# Sheet2.net
KiCad netlist of a schematic drawn in Altium Designer
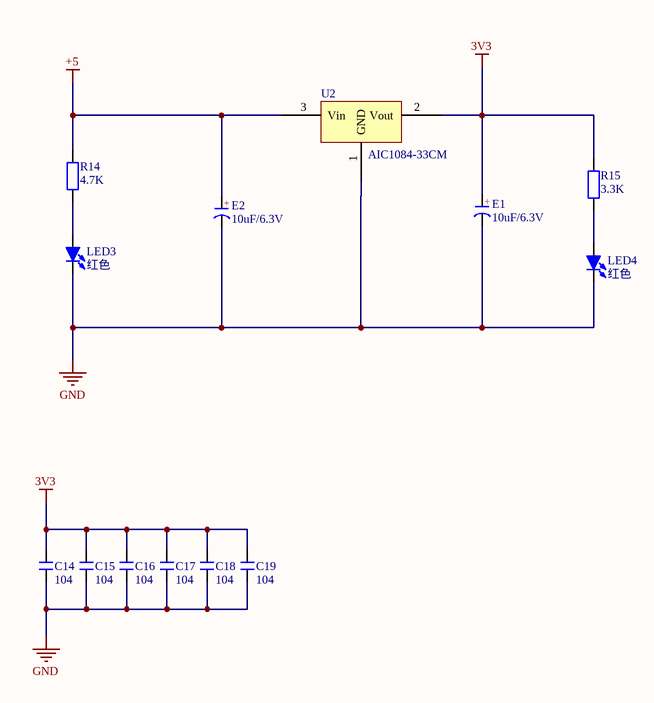
[diagram p0: Sheet2.SchDoc]

(export (version "E")
  (design (tool "Eeschema 10.0.6"))
  (components
    (comp (ref "C14")
      (value "104")
      (footprint "C 0603_L")
      (description "无极性贴片电容")
      (fields (field (name "版权归属") "源创客"))
      (libsource (lib "3.1   - 电阻-电容-电感") (part "C"))
    )
    (comp (ref "C15")
      (value "104")
      (footprint "C 0603_L")
      (description "无极性贴片电容")
      (fields (field (name "版权归属") "源创客"))
      (libsource (lib "3.1   - 电阻-电容-电感") (part "C"))
    )
    (comp (ref "C16")
      (value "104")
      (footprint "C 0603_L")
      (description "无极性贴片电容")
      (fields (field (name "版权归属") "源创客"))
      (libsource (lib "3.1   - 电阻-电容-电感") (part "C"))
    )
    (comp (ref "C17")
      (value "104")
      (footprint "C 0603_L")
      (description "无极性贴片电容")
      (fields (field (name "版权归属") "源创客"))
      (libsource (lib "3.1   - 电阻-电容-电感") (part "C"))
    )
    (comp (ref "C18")
      (value "104")
      (footprint "C 0603_L")
      (description "无极性贴片电容")
      (fields (field (name "版权归属") "源创客"))
      (libsource (lib "3.1   - 电阻-电容-电感") (part "C"))
    )
    (comp (ref "C19")
      (value "104")
      (footprint "C 0603_L")
      (description "无极性贴片电容")
      (fields (field (name "版权归属") "源创客"))
      (libsource (lib "3.1   - 电阻-电容-电感") (part "C"))
    )
    (comp (ref "E1")
      (value "10uF/6.3V")
      (footprint "CD A(3216)")
      (description "贴片钽电容")
      (fields (field (name "版权归属") "源创客"))
      (libsource (lib "3.1   - 电阻-电容-电感") (part "C-CD"))
    )
    (comp (ref "E2")
      (value "10uF/6.3V")
      (footprint "CD A(3216)")
      (description "贴片钽电容")
      (fields (field (name "版权归属") "源创客"))
      (libsource (lib "3.1   - 电阻-电容-电感") (part "C-CD"))
    )
    (comp (ref "LED3")
      (value "红色")
      (footprint "LED 0603R")
      (description "贴片LED")
      (fields (field (name "版权归属") "源创客"))
      (libsource (lib "9.1   - LED") (part "LED-SMD"))
    )
    (comp (ref "LED4")
      (value "红色")
      (footprint "LED 0603B")
      (description "贴片LED")
      (fields (field (name "版权归属") "源创客"))
      (libsource (lib "9.1   - LED") (part "LED-SMD"))
    )
    (comp (ref "R14")
      (value "4.7K")
      (footprint "R 0603_L")
      (description "贴片电阻")
      (fields (field (name "版权归属") "源创客"))
      (libsource (lib "3.1   - 电阻-电容-电感") (part "R"))
    )
    (comp (ref "R15")
      (value "3.3K")
      (footprint "R 0603_L")
      (description "贴片电阻")
      (fields (field (name "版权归属") "源创客"))
      (libsource (lib "3.1   - 电阻-电容-电感") (part "R"))
    )
    (comp (ref "U2")
      (value "AIC1084-33CM")
      (footprint "TO263-3B")
      (libsource (lib "power") (part "AIC1084-33CM"))
    )
  )
  (nets
    (net (code "1") (name "+5") (class "Default")
      (node (ref "E2") (pin "1") (pinfunction "A_1") (pintype "passive"))
      (node (ref "R14") (pin "1") (pinfunction "1_1") (pintype "passive"))
      (node (ref "U2") (pin "3") (pinfunction "Vin_3") (pintype "passive"))
    )
    (net (code "2") (name "3V3") (class "Default")
      (node (ref "C14") (pin "2") (pinfunction "2_2") (pintype "passive"))
      (node (ref "C15") (pin "2") (pinfunction "2_2") (pintype "passive"))
      (node (ref "C16") (pin "2") (pinfunction "2_2") (pintype "passive"))
      (node (ref "C17") (pin "2") (pinfunction "2_2") (pintype "passive"))
      (node (ref "C18") (pin "2") (pinfunction "2_2") (pintype "passive"))
      (node (ref "C19") (pin "2") (pinfunction "2_2") (pintype "passive"))
      (node (ref "E1") (pin "1") (pinfunction "A_1") (pintype "passive"))
      (node (ref "R15") (pin "1") (pinfunction "1_1") (pintype "passive"))
      (node (ref "U2") (pin "2") (pinfunction "Vout_2") (pintype "passive"))
    )
    (net (code "3") (name "GND") (class "Default")
      (node (ref "C14") (pin "1") (pinfunction "1_1") (pintype "passive"))
      (node (ref "C15") (pin "1") (pinfunction "1_1") (pintype "passive"))
      (node (ref "C16") (pin "1") (pinfunction "1_1") (pintype "passive"))
      (node (ref "C17") (pin "1") (pinfunction "1_1") (pintype "passive"))
      (node (ref "C18") (pin "1") (pinfunction "1_1") (pintype "passive"))
      (node (ref "C19") (pin "1") (pinfunction "1_1") (pintype "passive"))
      (node (ref "E1") (pin "2") (pinfunction "K_2") (pintype "passive"))
      (node (ref "E2") (pin "2") (pinfunction "K_2") (pintype "passive"))
      (node (ref "LED3") (pin "2") (pinfunction "K_2") (pintype "passive"))
      (node (ref "LED4") (pin "2") (pinfunction "K_2") (pintype "passive"))
      (node (ref "U2") (pin "1") (pinfunction "GND_1") (pintype "passive"))
    )
    (net (code "4") (name "Net-(LED3-A)") (class "Default")
      (node (ref "LED3") (pin "1") (pinfunction "A_1") (pintype "passive"))
      (node (ref "R14") (pin "2") (pinfunction "2_2") (pintype "passive"))
    )
    (net (code "5") (name "Net-(LED4-A)") (class "Default")
      (node (ref "LED4") (pin "1") (pinfunction "A_1") (pintype "passive"))
      (node (ref "R15") (pin "2") (pinfunction "2_2") (pintype "passive"))
    )
  )
)
